# IFM_DuberFilter_ThroughHole_PCB_REV1a.net
KiCad netlist of a schematic drawn in EAGLE
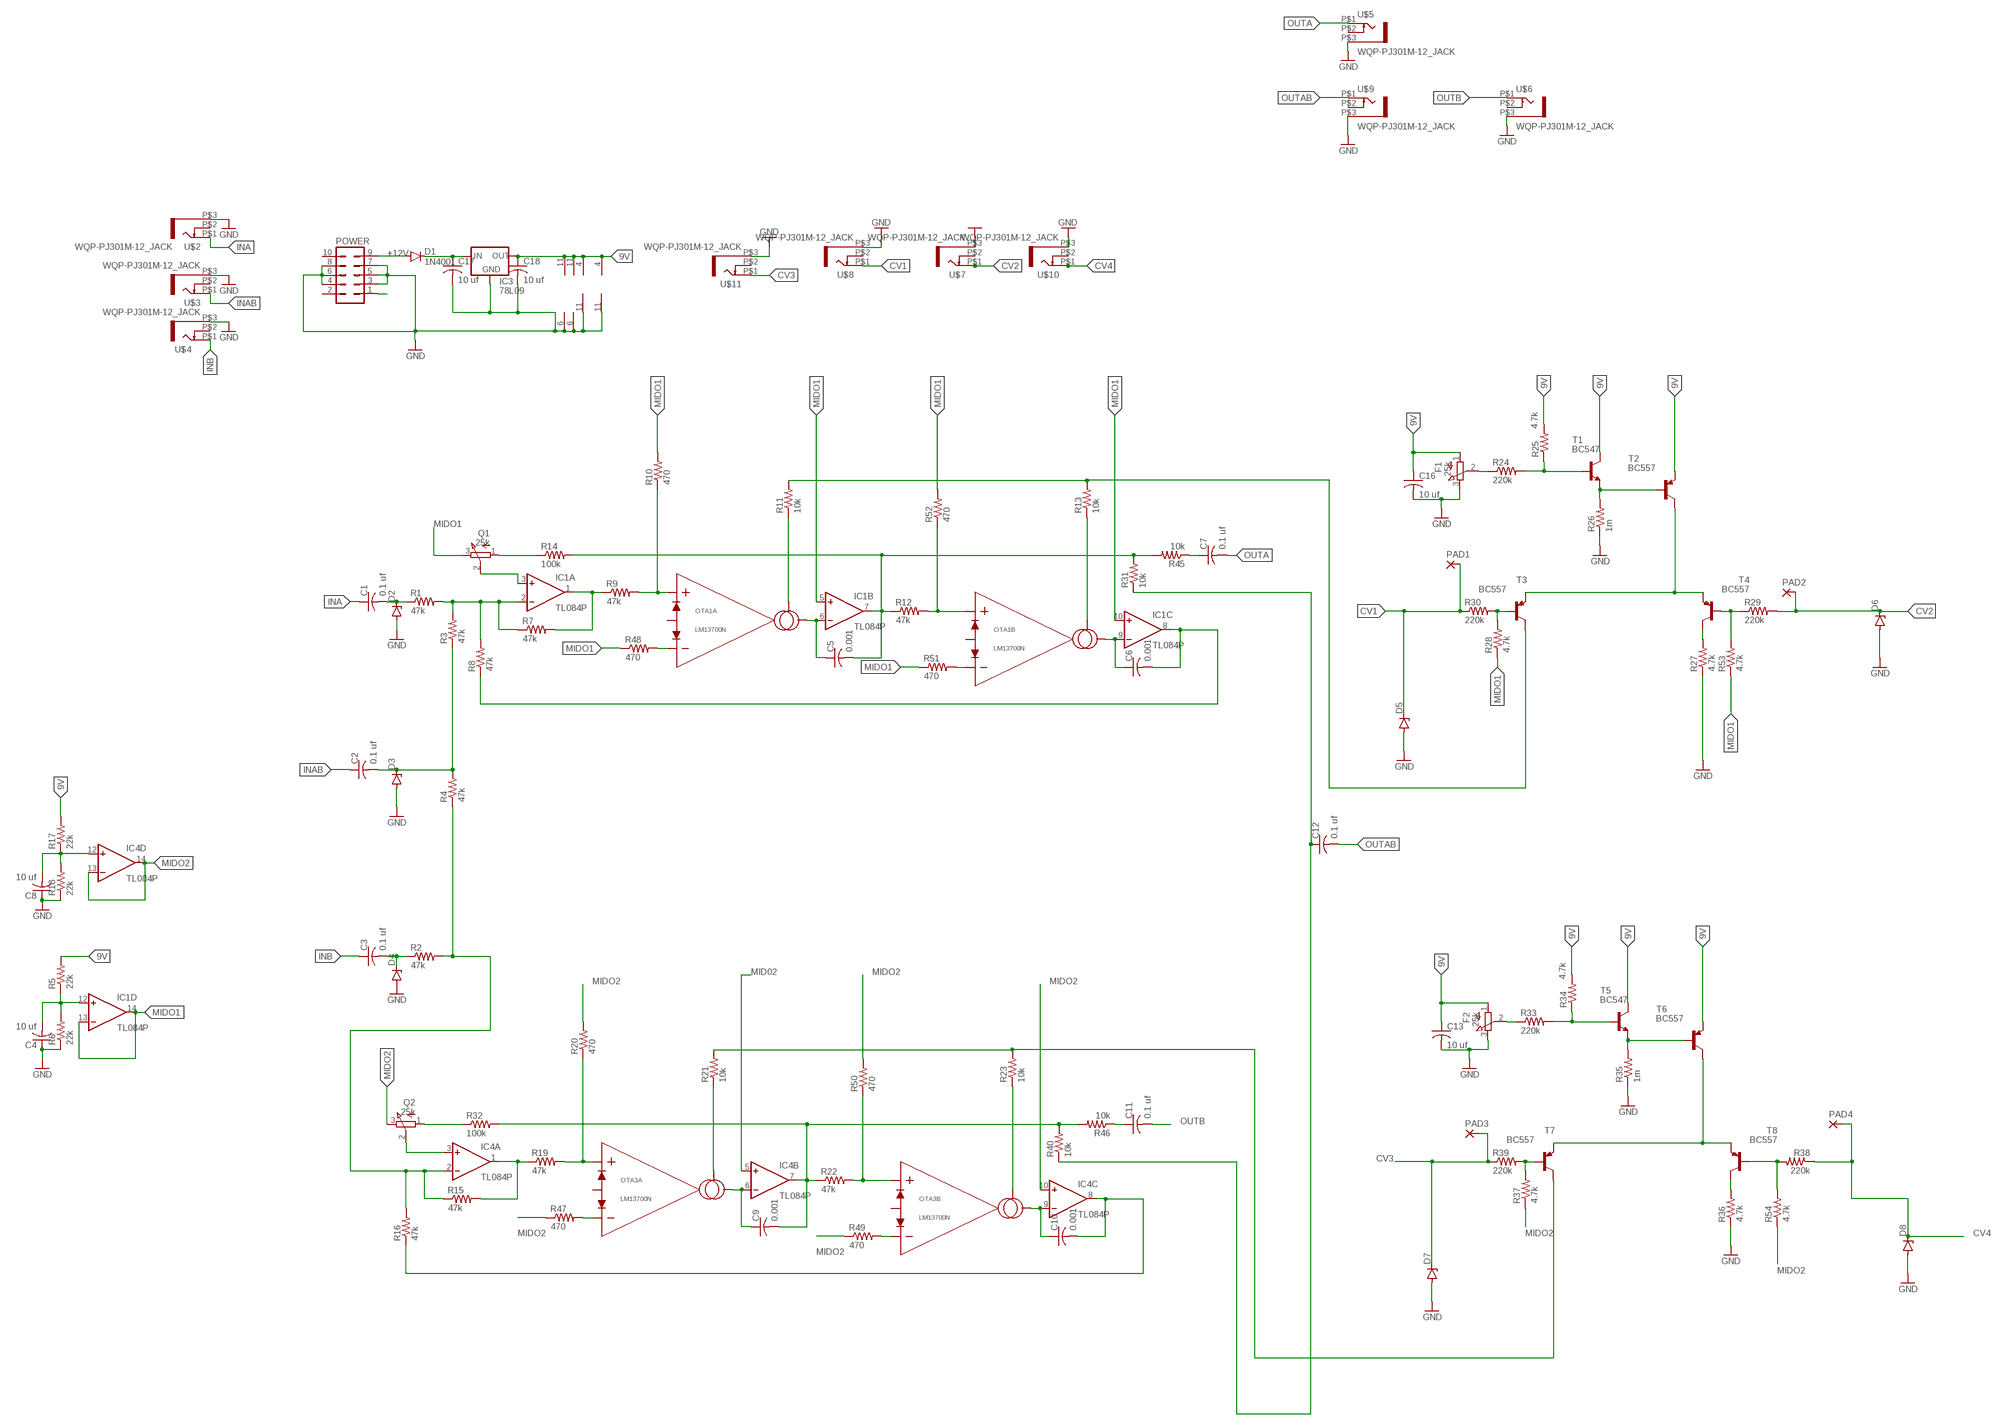
[diagram p0: schematic, sheet 1]

(export (version "E")
  (design (tool "Eeschema 10.0.6"))
  (components
    (comp (ref "C1")
      (value "0.1 uf")
      (footprint "eagle-import:C050-030X075")
      (libsource (lib "eagle-import") (part "C-US050-030X075"))
    )
    (comp (ref "C2")
      (value "0.1 uf")
      (footprint "eagle-import:C050-030X075")
      (libsource (lib "eagle-import") (part "C-US050-030X075"))
    )
    (comp (ref "C3")
      (value "0.1 uf")
      (footprint "eagle-import:C050-030X075")
      (libsource (lib "eagle-import") (part "C-US050-030X075"))
    )
    (comp (ref "C4")
      (value "10 uf")
      (footprint "eagle-import:C050-030X075")
      (libsource (lib "eagle-import") (part "C-US050-030X075"))
    )
    (comp (ref "C5")
      (value "0.001")
      (footprint "eagle-import:C050-030X075")
      (libsource (lib "eagle-import") (part "C-US050-030X075"))
    )
    (comp (ref "C6")
      (value "0.001")
      (footprint "eagle-import:C050-030X075")
      (libsource (lib "eagle-import") (part "C-US050-030X075"))
    )
    (comp (ref "C7")
      (value "0.1 uf")
      (footprint "eagle-import:C050-030X075")
      (libsource (lib "eagle-import") (part "C-US050-030X075"))
    )
    (comp (ref "C8")
      (value "10 uf")
      (footprint "eagle-import:C050-030X075")
      (libsource (lib "eagle-import") (part "C-US050-030X075"))
    )
    (comp (ref "C9")
      (value "0.001")
      (footprint "eagle-import:C050-030X075")
      (libsource (lib "eagle-import") (part "C-US050-030X075"))
    )
    (comp (ref "C10")
      (value "0.001")
      (footprint "eagle-import:C050-030X075")
      (libsource (lib "eagle-import") (part "C-US050-030X075"))
    )
    (comp (ref "C11")
      (value "0.1 uf")
      (footprint "eagle-import:C050-030X075")
      (libsource (lib "eagle-import") (part "C-US050-030X075"))
    )
    (comp (ref "C12")
      (value "0.1 uf")
      (footprint "eagle-import:C050-030X075")
      (libsource (lib "eagle-import") (part "C-US050-030X075"))
    )
    (comp (ref "C13")
      (value "10 uf")
      (footprint "eagle-import:C050-030X075")
      (libsource (lib "eagle-import") (part "C-US050-030X075"))
    )
    (comp (ref "C16")
      (value "10 uf")
      (footprint "eagle-import:C050-030X075")
      (libsource (lib "eagle-import") (part "C-US050-030X075"))
    )
    (comp (ref "C17")
      (value "10 uf")
      (footprint "eagle-import:C050-030X075")
      (libsource (lib "eagle-import") (part "C-US050-030X075"))
    )
    (comp (ref "C18")
      (value "10 uf")
      (footprint "eagle-import:C050-030X075")
      (libsource (lib "eagle-import") (part "C-US050-030X075"))
    )
    (comp (ref "D1")
      (value "1N4001")
      (footprint "eagle-import:DO41-10")
      (libsource (lib "eagle-import") (part "1N4004"))
    )
    (comp (ref "D2")
      (value "ZENER-DIODEDO34-7")
      (footprint "eagle-import:DO34Z7")
      (libsource (lib "eagle-import") (part "ZENER-DIODEDO34-7"))
    )
    (comp (ref "D3")
      (value "ZENER-DIODEDO34-7")
      (footprint "eagle-import:DO34Z7")
      (fields (field (name "SPICEPREFIX") "D"))
      (libsource (lib "eagle-import") (part "ZENER-DIODEDO34-7"))
    )
    (comp (ref "D4")
      (value "ZENER-DIODEDO34-7")
      (footprint "eagle-import:DO34Z7")
      (libsource (lib "eagle-import") (part "ZENER-DIODEDO34-7"))
    )
    (comp (ref "D5")
      (value "ZENER-DIODEDO34-7")
      (footprint "eagle-import:DO34Z7")
      (libsource (lib "eagle-import") (part "ZENER-DIODEDO34-7"))
    )
    (comp (ref "D6")
      (value "ZENER-DIODEDO34-7")
      (footprint "eagle-import:DO34Z7")
      (libsource (lib "eagle-import") (part "ZENER-DIODEDO34-7"))
    )
    (comp (ref "D7")
      (value "ZENER-DIODEDO34-7")
      (footprint "eagle-import:DO34Z7")
      (libsource (lib "eagle-import") (part "ZENER-DIODEDO34-7"))
    )
    (comp (ref "D8")
      (value "ZENER-DIODEDO34-7")
      (footprint "eagle-import:DO34Z7")
      (libsource (lib "eagle-import") (part "ZENER-DIODEDO34-7"))
    )
    (comp (ref "F1")
      (value "25k")
      (footprint "eagle-import:EVUFXL")
      (libsource (lib "eagle-import") (part "EVULF3"))
    )
    (comp (ref "F2")
      (value "25k")
      (footprint "eagle-import:EVUFXL")
      (libsource (lib "eagle-import") (part "EVULF3"))
    )
    (comp (ref "IC1")
      (value "TL084P")
      (footprint "eagle-import:DIL14")
      (libsource (lib "eagle-import") (part "TL084P"))
    )
    (comp (ref "IC3")
      (value "78L09")
      (footprint "eagle-import:78LXX")
      (libsource (lib "eagle-import") (part "78LXX"))
    )
    (comp (ref "IC4")
      (value "TL084P")
      (footprint "eagle-import:DIL14")
      (libsource (lib "eagle-import") (part "TL084P"))
    )
    (comp (ref "OTA1")
      (value "LM13700N")
      (footprint "eagle-import:DIP16")
      (libsource (lib "eagle-import") (part "LM13700N"))
    )
    (comp (ref "OTA3")
      (value "LM13700N")
      (footprint "eagle-import:DIP16")
      (libsource (lib "eagle-import") (part "LM13700N"))
    )
    (comp (ref "PAD1")
      (value "SMD2")
      (footprint "eagle-import:SMD1,27-2,54")
      (libsource (lib "eagle-import") (part "SMD2"))
    )
    (comp (ref "PAD2")
      (value "SMD2")
      (footprint "eagle-import:SMD1,27-2,54")
      (libsource (lib "eagle-import") (part "SMD2"))
    )
    (comp (ref "PAD3")
      (value "SMD2")
      (footprint "eagle-import:SMD1,27-2,54")
      (libsource (lib "eagle-import") (part "SMD2"))
    )
    (comp (ref "PAD4")
      (value "SMD2")
      (footprint "eagle-import:SMD1,27-2,54")
      (libsource (lib "eagle-import") (part "SMD2"))
    )
    (comp (ref "POWER")
      (value "10_PIN_HEADER")
      (footprint "eagle-import:MA05-2")
      (libsource (lib "eagle-import") (part "10_PIN_HEADER"))
    )
    (comp (ref "Q1")
      (value "25k")
      (footprint "eagle-import:EVUFXL")
      (libsource (lib "eagle-import") (part "EVULF3"))
    )
    (comp (ref "Q2")
      (value "25k")
      (footprint "eagle-import:EVUFXL")
      (libsource (lib "eagle-import") (part "EVULF3"))
    )
    (comp (ref "R1")
      (value "47k")
      (footprint "eagle-import:0204_7")
      (libsource (lib "eagle-import") (part "R-US_0204/7"))
    )
    (comp (ref "R2")
      (value "47k")
      (footprint "eagle-import:0204_7")
      (libsource (lib "eagle-import") (part "R-US_0204/7"))
    )
    (comp (ref "R3")
      (value "47k")
      (footprint "eagle-import:0204_7")
      (libsource (lib "eagle-import") (part "R-US_0204/7"))
    )
    (comp (ref "R4")
      (value "47k")
      (footprint "eagle-import:0204_7")
      (libsource (lib "eagle-import") (part "R-US_0204/7"))
    )
    (comp (ref "R5")
      (value "22k")
      (footprint "eagle-import:0204_7")
      (libsource (lib "eagle-import") (part "R-US_0204/7"))
    )
    (comp (ref "R6")
      (value "22k")
      (footprint "eagle-import:0204_7")
      (libsource (lib "eagle-import") (part "R-US_0204/7"))
    )
    (comp (ref "R7")
      (value "47k")
      (footprint "eagle-import:0204_7")
      (libsource (lib "eagle-import") (part "R-US_0204/7"))
    )
    (comp (ref "R8")
      (value "47k")
      (footprint "eagle-import:0204_7")
      (libsource (lib "eagle-import") (part "R-US_0204/7"))
    )
    (comp (ref "R9")
      (value "47k")
      (footprint "eagle-import:0204_7")
      (libsource (lib "eagle-import") (part "R-US_0204/7"))
    )
    (comp (ref "R10")
      (value "470")
      (footprint "eagle-import:0204_7")
      (libsource (lib "eagle-import") (part "R-US_0204/7"))
    )
    (comp (ref "R11")
      (value "10k")
      (footprint "eagle-import:0204_7")
      (libsource (lib "eagle-import") (part "R-US_0204/7"))
    )
    (comp (ref "R12")
      (value "47k")
      (footprint "eagle-import:0204_7")
      (libsource (lib "eagle-import") (part "R-US_0204/7"))
    )
    (comp (ref "R13")
      (value "10k")
      (footprint "eagle-import:0204_7")
      (libsource (lib "eagle-import") (part "R-US_0204/7"))
    )
    (comp (ref "R14")
      (value "100k")
      (footprint "eagle-import:0204_7")
      (libsource (lib "eagle-import") (part "R-US_0204/7"))
    )
    (comp (ref "R15")
      (value "47k")
      (footprint "eagle-import:0204_7")
      (libsource (lib "eagle-import") (part "R-US_0204/7"))
    )
    (comp (ref "R16")
      (value "47k")
      (footprint "eagle-import:0204_7")
      (libsource (lib "eagle-import") (part "R-US_0204/7"))
    )
    (comp (ref "R17")
      (value "22k")
      (footprint "eagle-import:0204_7")
      (libsource (lib "eagle-import") (part "R-US_0204/7"))
    )
    (comp (ref "R18")
      (value "22k")
      (footprint "eagle-import:0204_7")
      (libsource (lib "eagle-import") (part "R-US_0204/7"))
    )
    (comp (ref "R19")
      (value "47k")
      (footprint "eagle-import:0204_7")
      (libsource (lib "eagle-import") (part "R-US_0204/7"))
    )
    (comp (ref "R20")
      (value "470")
      (footprint "eagle-import:0204_7")
      (libsource (lib "eagle-import") (part "R-US_0204/7"))
    )
    (comp (ref "R21")
      (value "10k")
      (footprint "eagle-import:0204_7")
      (libsource (lib "eagle-import") (part "R-US_0204/7"))
    )
    (comp (ref "R22")
      (value "47k")
      (footprint "eagle-import:0204_7")
      (libsource (lib "eagle-import") (part "R-US_0204/7"))
    )
    (comp (ref "R23")
      (value "10k")
      (footprint "eagle-import:0204_7")
      (libsource (lib "eagle-import") (part "R-US_0204/7"))
    )
    (comp (ref "R24")
      (value "220k")
      (footprint "eagle-import:0204_7")
      (libsource (lib "eagle-import") (part "R-US_0204/7"))
    )
    (comp (ref "R25")
      (value "4.7k")
      (footprint "eagle-import:0204_7")
      (libsource (lib "eagle-import") (part "R-US_0204/7"))
    )
    (comp (ref "R26")
      (value "1m")
      (footprint "eagle-import:0204_7")
      (libsource (lib "eagle-import") (part "R-US_0204/7"))
    )
    (comp (ref "R27")
      (value "4.7k")
      (footprint "eagle-import:0204_7")
      (libsource (lib "eagle-import") (part "R-US_0204/7"))
    )
    (comp (ref "R28")
      (value "4.7k")
      (footprint "eagle-import:0204_7")
      (libsource (lib "eagle-import") (part "R-US_0204/7"))
    )
    (comp (ref "R29")
      (value "220k")
      (footprint "eagle-import:0204_7")
      (libsource (lib "eagle-import") (part "R-US_0204/7"))
    )
    (comp (ref "R30")
      (value "220k")
      (footprint "eagle-import:0204_7")
      (libsource (lib "eagle-import") (part "R-US_0204/7"))
    )
    (comp (ref "R31")
      (value "10k")
      (footprint "eagle-import:0204_7")
      (libsource (lib "eagle-import") (part "R-US_0204/7"))
    )
    (comp (ref "R32")
      (value "100k")
      (footprint "eagle-import:0204_7")
      (libsource (lib "eagle-import") (part "R-US_0204/7"))
    )
    (comp (ref "R33")
      (value "220k")
      (footprint "eagle-import:0204_7")
      (libsource (lib "eagle-import") (part "R-US_0204/7"))
    )
    (comp (ref "R34")
      (value "4.7k")
      (footprint "eagle-import:0204_7")
      (libsource (lib "eagle-import") (part "R-US_0204/7"))
    )
    (comp (ref "R35")
      (value "1m")
      (footprint "eagle-import:0204_7")
      (libsource (lib "eagle-import") (part "R-US_0204/7"))
    )
    (comp (ref "R36")
      (value "4.7k")
      (footprint "eagle-import:0204_7")
      (libsource (lib "eagle-import") (part "R-US_0204/7"))
    )
    (comp (ref "R37")
      (value "4.7k")
      (footprint "eagle-import:0204_7")
      (libsource (lib "eagle-import") (part "R-US_0204/7"))
    )
    (comp (ref "R38")
      (value "220k")
      (footprint "eagle-import:0204_7")
      (libsource (lib "eagle-import") (part "R-US_0204/7"))
    )
    (comp (ref "R39")
      (value "220k")
      (footprint "eagle-import:0204_7")
      (libsource (lib "eagle-import") (part "R-US_0204/7"))
    )
    (comp (ref "R40")
      (value "10k")
      (footprint "eagle-import:0204_7")
      (libsource (lib "eagle-import") (part "R-US_0204/7"))
    )
    (comp (ref "R45")
      (value "10k")
      (footprint "eagle-import:0204_7")
      (libsource (lib "eagle-import") (part "R-US_0204/7"))
    )
    (comp (ref "R46")
      (value "10k")
      (footprint "eagle-import:0204_7")
      (libsource (lib "eagle-import") (part "R-US_0204/7"))
    )
    (comp (ref "R47")
      (value "470")
      (footprint "eagle-import:0204_7")
      (libsource (lib "eagle-import") (part "R-US_0204/7"))
    )
    (comp (ref "R48")
      (value "470")
      (footprint "eagle-import:0204_7")
      (libsource (lib "eagle-import") (part "R-US_0204/7"))
    )
    (comp (ref "R49")
      (value "470")
      (footprint "eagle-import:0204_7")
      (libsource (lib "eagle-import") (part "R-US_0204/7"))
    )
    (comp (ref "R50")
      (value "470")
      (footprint "eagle-import:0204_7")
      (libsource (lib "eagle-import") (part "R-US_0204/7"))
    )
    (comp (ref "R51")
      (value "470")
      (footprint "eagle-import:0204_7")
      (libsource (lib "eagle-import") (part "R-US_0204/7"))
    )
    (comp (ref "R52")
      (value "470")
      (footprint "eagle-import:0204_7")
      (libsource (lib "eagle-import") (part "R-US_0204/7"))
    )
    (comp (ref "R53")
      (value "4.7k")
      (footprint "eagle-import:0204_7")
      (libsource (lib "eagle-import") (part "R-US_0204/7"))
    )
    (comp (ref "R54")
      (value "4.7k")
      (footprint "eagle-import:0204_7")
      (libsource (lib "eagle-import") (part "R-US_0204/7"))
    )
    (comp (ref "T1")
      (value "BC547")
      (footprint "eagle-import:TO92")
      (libsource (lib "eagle-import") (part "BC547"))
    )
    (comp (ref "T2")
      (value "BC557")
      (footprint "eagle-import:TO92-EBC")
      (libsource (lib "eagle-import") (part "-PNP-TO92-EBCBC557A"))
    )
    (comp (ref "T3")
      (value "BC557")
      (footprint "eagle-import:TO92-EBC")
      (libsource (lib "eagle-import") (part "-PNP-TO92-EBCBC557A"))
    )
    (comp (ref "T4")
      (value "BC557")
      (footprint "eagle-import:TO92-EBC")
      (libsource (lib "eagle-import") (part "-PNP-TO92-EBCBC557A"))
    )
    (comp (ref "T5")
      (value "BC547")
      (footprint "eagle-import:TO92")
      (libsource (lib "eagle-import") (part "BC547"))
    )
    (comp (ref "T6")
      (value "BC557")
      (footprint "eagle-import:TO92-EBC")
      (libsource (lib "eagle-import") (part "-PNP-TO92-EBCBC557A"))
    )
    (comp (ref "T7")
      (value "BC557")
      (footprint "eagle-import:TO92-EBC")
      (libsource (lib "eagle-import") (part "-PNP-TO92-EBCBC557A"))
    )
    (comp (ref "T8")
      (value "BC557")
      (footprint "eagle-import:TO92-EBC")
      (libsource (lib "eagle-import") (part "-PNP-TO92-EBCBC557A"))
    )
    (comp (ref "U$2")
      (value "WQP-PJ301M-12_JACK")
      (footprint "eagle-import:WQP-PJ301M-12_JACK")
      (libsource (lib "eagle-import") (part "WQP-PJ301M-12_JACK"))
    )
    (comp (ref "U$3")
      (value "WQP-PJ301M-12_JACK")
      (footprint "eagle-import:WQP-PJ301M-12_JACK")
      (libsource (lib "eagle-import") (part "WQP-PJ301M-12_JACK"))
    )
    (comp (ref "U$4")
      (value "WQP-PJ301M-12_JACK")
      (footprint "eagle-import:WQP-PJ301M-12_JACK")
      (libsource (lib "eagle-import") (part "WQP-PJ301M-12_JACK"))
    )
    (comp (ref "U$5")
      (value "WQP-PJ301M-12_JACK")
      (footprint "eagle-import:WQP-PJ301M-12_JACK")
      (libsource (lib "eagle-import") (part "WQP-PJ301M-12_JACK"))
    )
    (comp (ref "U$6")
      (value "WQP-PJ301M-12_JACK")
      (footprint "eagle-import:WQP-PJ301M-12_JACK")
      (libsource (lib "eagle-import") (part "WQP-PJ301M-12_JACK"))
    )
    (comp (ref "U$7")
      (value "WQP-PJ301M-12_JACK")
      (footprint "eagle-import:WQP-PJ301M-12_JACK")
      (libsource (lib "eagle-import") (part "WQP-PJ301M-12_JACK"))
    )
    (comp (ref "U$8")
      (value "WQP-PJ301M-12_JACK")
      (footprint "eagle-import:WQP-PJ301M-12_JACK")
      (libsource (lib "eagle-import") (part "WQP-PJ301M-12_JACK"))
    )
    (comp (ref "U$9")
      (value "WQP-PJ301M-12_JACK")
      (footprint "eagle-import:WQP-PJ301M-12_JACK")
      (libsource (lib "eagle-import") (part "WQP-PJ301M-12_JACK"))
    )
    (comp (ref "U$10")
      (value "WQP-PJ301M-12_JACK")
      (footprint "eagle-import:WQP-PJ301M-12_JACK")
      (libsource (lib "eagle-import") (part "WQP-PJ301M-12_JACK"))
    )
    (comp (ref "U$11")
      (value "WQP-PJ301M-12_JACK")
      (footprint "eagle-import:WQP-PJ301M-12_JACK")
      (libsource (lib "eagle-import") (part "WQP-PJ301M-12_JACK"))
    )
  )
  (nets
    (net (code "1") (name "/+12V") (class "Default")
      (node (ref "C17") (pin "1") (pinfunction "1_1") (pintype "passive"))
      (node (ref "D1") (pin "C") (pinfunction "C_C") (pintype "passive"))
      (node (ref "IC3") (pin "IN") (pinfunction "IN_IN") (pintype "input"))
    )
    (net (code "2") (name "/MID02") (class "Default")
      (node (ref "IC4") (pin "5") (pinfunction "+IN_5") (pintype "input"))
    )
    (net (code "3") (name "9V") (class "Default")
      (node (ref "C13") (pin "1") (pinfunction "1_1") (pintype "passive"))
      (node (ref "C16") (pin "1") (pinfunction "1_1") (pintype "passive"))
      (node (ref "C18") (pin "1") (pinfunction "1_1") (pintype "passive"))
      (node (ref "F1") (pin "1") (pinfunction "A_1") (pintype "passive"))
      (node (ref "F2") (pin "1") (pinfunction "A_1") (pintype "passive"))
      (node (ref "IC1") (pin "4") (pinfunction "V+_4") (pintype "power_in"))
      (node (ref "IC3") (pin "OUT") (pinfunction "OUT_OUT") (pintype "passive"))
      (node (ref "IC4") (pin "4") (pinfunction "V+_4") (pintype "power_in"))
      (node (ref "OTA1") (pin "11") (pinfunction "VCC_11") (pintype "power_in"))
      (node (ref "OTA3") (pin "11") (pinfunction "VCC_11") (pintype "power_in"))
      (node (ref "R17") (pin "2") (pinfunction "2_2") (pintype "passive"))
      (node (ref "R25") (pin "2") (pinfunction "2_2") (pintype "passive"))
      (node (ref "R34") (pin "2") (pinfunction "2_2") (pintype "passive"))
      (node (ref "R5") (pin "2") (pinfunction "2_2") (pintype "passive"))
      (node (ref "T1") (pin "3") (pinfunction "C_3") (pintype "passive"))
      (node (ref "T2") (pin "E") (pinfunction "E_E") (pintype "passive"))
      (node (ref "T5") (pin "3") (pinfunction "C_3") (pintype "passive"))
      (node (ref "T6") (pin "E") (pinfunction "E_E") (pintype "passive"))
    )
    (net (code "4") (name "CV1") (class "Default")
      (node (ref "D5") (pin "C") (pinfunction "C_C") (pintype "passive"))
      (node (ref "PAD1") (pin "1") (pinfunction "P_1") (pintype "passive"))
      (node (ref "R30") (pin "1") (pinfunction "1_1") (pintype "passive"))
      (node (ref "U$8") (pin "P$1") (pinfunction "2_P$1") (pintype "passive"))
    )
    (net (code "5") (name "CV2") (class "Default")
      (node (ref "D6") (pin "C") (pinfunction "C_C") (pintype "passive"))
      (node (ref "PAD2") (pin "1") (pinfunction "P_1") (pintype "passive"))
      (node (ref "R29") (pin "2") (pinfunction "2_2") (pintype "passive"))
      (node (ref "U$7") (pin "P$1") (pinfunction "2_P$1") (pintype "passive"))
    )
    (net (code "6") (name "CV3") (class "Default")
      (node (ref "D7") (pin "C") (pinfunction "C_C") (pintype "passive"))
      (node (ref "PAD3") (pin "1") (pinfunction "P_1") (pintype "passive"))
      (node (ref "R39") (pin "1") (pinfunction "1_1") (pintype "passive"))
      (node (ref "U$11") (pin "P$1") (pinfunction "2_P$1") (pintype "passive"))
    )
    (net (code "7") (name "CV4") (class "Default")
      (node (ref "D8") (pin "C") (pinfunction "C_C") (pintype "passive"))
      (node (ref "PAD4") (pin "1") (pinfunction "P_1") (pintype "passive"))
      (node (ref "R38") (pin "1") (pinfunction "1_1") (pintype "passive"))
      (node (ref "U$10") (pin "P$1") (pinfunction "2_P$1") (pintype "passive"))
    )
    (net (code "8") (name "GND") (class "Default")
      (node (ref "C13") (pin "2") (pinfunction "2_2") (pintype "passive"))
      (node (ref "C16") (pin "2") (pinfunction "2_2") (pintype "passive"))
      (node (ref "C17") (pin "2") (pinfunction "2_2") (pintype "passive"))
      (node (ref "C18") (pin "2") (pinfunction "2_2") (pintype "passive"))
      (node (ref "C4") (pin "1") (pinfunction "1_1") (pintype "passive"))
      (node (ref "C8") (pin "1") (pinfunction "1_1") (pintype "passive"))
      (node (ref "D2") (pin "A") (pinfunction "A_A") (pintype "passive"))
      (node (ref "D3") (pin "A") (pinfunction "A_A") (pintype "passive"))
      (node (ref "D4") (pin "A") (pinfunction "A_A") (pintype "passive"))
      (node (ref "D5") (pin "A") (pinfunction "A_A") (pintype "passive"))
      (node (ref "D6") (pin "A") (pinfunction "A_A") (pintype "passive"))
      (node (ref "D7") (pin "A") (pinfunction "A_A") (pintype "passive"))
      (node (ref "D8") (pin "A") (pinfunction "A_A") (pintype "passive"))
      (node (ref "F1") (pin "3") (pinfunction "E_3") (pintype "passive"))
      (node (ref "F2") (pin "3") (pinfunction "E_3") (pintype "passive"))
      (node (ref "IC1") (pin "11") (pinfunction "V-_11") (pintype "power_in"))
      (node (ref "IC3") (pin "GND") (pinfunction "GND_GND") (pintype "input"))
      (node (ref "IC4") (pin "11") (pinfunction "V-_11") (pintype "power_in"))
      (node (ref "OTA1") (pin "6") (pinfunction "VEE_6") (pintype "power_in"))
      (node (ref "OTA3") (pin "6") (pinfunction "VEE_6") (pintype "power_in"))
      (node (ref "POWER") (pin "3") (pinfunction "3_3") (pintype "passive"))
      (node (ref "POWER") (pin "4") (pinfunction "4_4") (pintype "passive"))
      (node (ref "POWER") (pin "5") (pinfunction "5_5") (pintype "passive"))
      (node (ref "POWER") (pin "6") (pinfunction "6_6") (pintype "passive"))
      (node (ref "POWER") (pin "7") (pinfunction "7_7") (pintype "passive"))
      (node (ref "POWER") (pin "8") (pinfunction "8_8") (pintype "passive"))
      (node (ref "R18") (pin "1") (pinfunction "1_1") (pintype "passive"))
      (node (ref "R26") (pin "1") (pinfunction "1_1") (pintype "passive"))
      (node (ref "R27") (pin "1") (pinfunction "1_1") (pintype "passive"))
      (node (ref "R35") (pin "1") (pinfunction "1_1") (pintype "passive"))
      (node (ref "R36") (pin "1") (pinfunction "1_1") (pintype "passive"))
      (node (ref "R6") (pin "1") (pinfunction "1_1") (pintype "passive"))
      (node (ref "U$10") (pin "P$3") (pinfunction "1_P$3") (pintype "passive"))
      (node (ref "U$11") (pin "P$3") (pinfunction "1_P$3") (pintype "passive"))
      (node (ref "U$2") (pin "P$3") (pinfunction "1_P$3") (pintype "passive"))
      (node (ref "U$3") (pin "P$3") (pinfunction "1_P$3") (pintype "passive"))
      (node (ref "U$4") (pin "P$3") (pinfunction "1_P$3") (pintype "passive"))
      (node (ref "U$5") (pin "P$3") (pinfunction "1_P$3") (pintype "passive"))
      (node (ref "U$6") (pin "P$3") (pinfunction "1_P$3") (pintype "passive"))
      (node (ref "U$7") (pin "P$3") (pinfunction "1_P$3") (pintype "passive"))
      (node (ref "U$8") (pin "P$3") (pinfunction "1_P$3") (pintype "passive"))
      (node (ref "U$9") (pin "P$3") (pinfunction "1_P$3") (pintype "passive"))
    )
    (net (code "9") (name "INA") (class "Default")
      (node (ref "C1") (pin "1") (pinfunction "1_1") (pintype "passive"))
      (node (ref "U$2") (pin "P$1") (pinfunction "2_P$1") (pintype "passive"))
    )
    (net (code "10") (name "INAB") (class "Default")
      (node (ref "C2") (pin "1") (pinfunction "1_1") (pintype "passive"))
      (node (ref "U$3") (pin "P$1") (pinfunction "2_P$1") (pintype "passive"))
    )
    (net (code "11") (name "INB") (class "Default")
      (node (ref "C3") (pin "1") (pinfunction "1_1") (pintype "passive"))
      (node (ref "U$4") (pin "P$1") (pinfunction "2_P$1") (pintype "passive"))
    )
    (net (code "12") (name "MIDO1") (class "Default")
      (node (ref "IC1") (pin "10") (pinfunction "+IN_10") (pintype "input"))
      (node (ref "IC1") (pin "13") (pinfunction "-IN_13") (pintype "input"))
      (node (ref "IC1") (pin "14") (pinfunction "OUT_14") (pintype "output"))
      (node (ref "IC1") (pin "5") (pinfunction "+IN_5") (pintype "input"))
      (node (ref "Q1") (pin "3") (pinfunction "E_3") (pintype "passive"))
      (node (ref "R10") (pin "2") (pinfunction "2_2") (pintype "passive"))
      (node (ref "R28") (pin "1") (pinfunction "1_1") (pintype "passive"))
      (node (ref "R48") (pin "1") (pinfunction "1_1") (pintype "passive"))
      (node (ref "R51") (pin "1") (pinfunction "1_1") (pintype "passive"))
      (node (ref "R52") (pin "2") (pinfunction "2_2") (pintype "passive"))
      (node (ref "R53") (pin "1") (pinfunction "1_1") (pintype "passive"))
    )
    (net (code "13") (name "MIDO2") (class "Default")
      (node (ref "IC4") (pin "10") (pinfunction "+IN_10") (pintype "input"))
      (node (ref "IC4") (pin "13") (pinfunction "-IN_13") (pintype "input"))
      (node (ref "IC4") (pin "14") (pinfunction "OUT_14") (pintype "output"))
      (node (ref "Q2") (pin "3") (pinfunction "E_3") (pintype "passive"))
      (node (ref "R20") (pin "2") (pinfunction "2_2") (pintype "passive"))
      (node (ref "R37") (pin "1") (pinfunction "1_1") (pintype "passive"))
      (node (ref "R47") (pin "1") (pinfunction "1_1") (pintype "passive"))
      (node (ref "R49") (pin "1") (pinfunction "1_1") (pintype "passive"))
      (node (ref "R50") (pin "2") (pinfunction "2_2") (pintype "passive"))
      (node (ref "R54") (pin "1") (pinfunction "1_1") (pintype "passive"))
    )
    (net (code "14") (name "Net-(C1-Pad2)") (class "Default")
      (node (ref "C1") (pin "2") (pinfunction "2_2") (pintype "passive"))
      (node (ref "D2") (pin "C") (pinfunction "C_C") (pintype "passive"))
      (node (ref "R1") (pin "1") (pinfunction "1_1") (pintype "passive"))
    )
    (net (code "15") (name "Net-(C2-Pad2)") (class "Default")
      (node (ref "C2") (pin "2") (pinfunction "2_2") (pintype "passive"))
      (node (ref "D3") (pin "C") (pinfunction "C_C") (pintype "passive"))
      (node (ref "R3") (pin "1") (pinfunction "1_1") (pintype "passive"))
      (node (ref "R4") (pin "2") (pinfunction "2_2") (pintype "passive"))
    )
    (net (code "16") (name "Net-(C3-Pad2)") (class "Default")
      (node (ref "C3") (pin "2") (pinfunction "2_2") (pintype "passive"))
      (node (ref "D4") (pin "C") (pinfunction "C_C") (pintype "passive"))
      (node (ref "R2") (pin "1") (pinfunction "1_1") (pintype "passive"))
    )
    (net (code "17") (name "Net-(C7-Pad1)") (class "Default")
      (node (ref "C7") (pin "1") (pinfunction "1_1") (pintype "passive"))
      (node (ref "R45") (pin "1") (pinfunction "1_1") (pintype "passive"))
    )
    (net (code "18") (name "Net-(C11-Pad1)") (class "Default")
      (node (ref "C11") (pin "1") (pinfunction "1_1") (pintype "passive"))
      (node (ref "R46") (pin "1") (pinfunction "1_1") (pintype "passive"))
    )
    (net (code "19") (name "Net-(C12-Pad1)") (class "Default")
      (node (ref "C12") (pin "1") (pinfunction "1_1") (pintype "passive"))
      (node (ref "R31") (pin "1") (pinfunction "1_1") (pintype "passive"))
      (node (ref "R40") (pin "1") (pinfunction "1_1") (pintype "passive"))
    )
    (net (code "20") (name "Net-(D1-PadA)") (class "Default")
      (node (ref "D1") (pin "A") (pinfunction "A_A") (pintype "passive"))
      (node (ref "POWER") (pin "9") (pinfunction "9_9") (pintype "passive"))
    )
    (net (code "21") (name "Net-(F1-S)") (class "Default")
      (node (ref "F1") (pin "2") (pinfunction "S_2") (pintype "passive"))
      (node (ref "R24") (pin "1") (pinfunction "1_1") (pintype "passive"))
    )
    (net (code "22") (name "Net-(F2-S)") (class "Default")
      (node (ref "F2") (pin "2") (pinfunction "S_2") (pintype "passive"))
      (node (ref "R33") (pin "1") (pinfunction "1_1") (pintype "passive"))
    )
    (net (code "23") (name "Net-(IC1A-+IN)") (class "Default")
      (node (ref "IC1") (pin "3") (pinfunction "+IN_3") (pintype "input"))
      (node (ref "Q1") (pin "2") (pinfunction "S_2") (pintype "passive"))
    )
    (net (code "24") (name "Net-(IC1A--IN)") (class "Default")
      (node (ref "IC1") (pin "2") (pinfunction "-IN_2") (pintype "input"))
      (node (ref "R1") (pin "2") (pinfunction "2_2") (pintype "passive"))
      (node (ref "R3") (pin "2") (pinfunction "2_2") (pintype "passive"))
      (node (ref "R7") (pin "1") (pinfunction "1_1") (pintype "passive"))
      (node (ref "R8") (pin "2") (pinfunction "2_2") (pintype "passive"))
    )
    (net (code "25") (name "Net-(IC1A-OUT)") (class "Default")
      (node (ref "IC1") (pin "1") (pinfunction "OUT_1") (pintype "output"))
      (node (ref "R7") (pin "2") (pinfunction "2_2") (pintype "passive"))
      (node (ref "R9") (pin "1") (pinfunction "1_1") (pintype "passive"))
    )
    (net (code "26") (name "Net-(IC1B--IN)") (class "Default")
      (node (ref "C5") (pin "1") (pinfunction "1_1") (pintype "passive"))
      (node (ref "IC1") (pin "6") (pinfunction "-IN_6") (pintype "input"))
      (node (ref "OTA1") (pin "5") (pinfunction "IOUT_5") (pintype "output"))
    )
    (net (code "27") (name "Net-(IC1B-OUT)") (class "Default")
      (node (ref "C5") (pin "2") (pinfunction "2_2") (pintype "passive"))
      (node (ref "IC1") (pin "7") (pinfunction "OUT_7") (pintype "output"))
      (node (ref "R12") (pin "1") (pinfunction "1_1") (pintype "passive"))
      (node (ref "R14") (pin "2") (pinfunction "2_2") (pintype "passive"))
      (node (ref "R31") (pin "2") (pinfunction "2_2") (pintype "passive"))
      (node (ref "R45") (pin "2") (pinfunction "2_2") (pintype "passive"))
    )
    (net (code "28") (name "Net-(IC1C--IN)") (class "Default")
      (node (ref "C6") (pin "1") (pinfunction "1_1") (pintype "passive"))
      (node (ref "IC1") (pin "9") (pinfunction "-IN_9") (pintype "input"))
      (node (ref "OTA1") (pin "12") (pinfunction "IOUT_12") (pintype "output"))
    )
    (net (code "29") (name "Net-(IC1C-OUT)") (class "Default")
      (node (ref "C6") (pin "2") (pinfunction "2_2") (pintype "passive"))
      (node (ref "IC1") (pin "8") (pinfunction "OUT_8") (pintype "output"))
      (node (ref "R8") (pin "1") (pinfunction "1_1") (pintype "passive"))
    )
    (net (code "30") (name "Net-(IC1D-+IN)") (class "Default")
      (node (ref "C4") (pin "2") (pinfunction "2_2") (pintype "passive"))
      (node (ref "IC1") (pin "12") (pinfunction "+IN_12") (pintype "input"))
      (node (ref "R5") (pin "1") (pinfunction "1_1") (pintype "passive"))
      (node (ref "R6") (pin "2") (pinfunction "2_2") (pintype "passive"))
    )
    (net (code "31") (name "Net-(IC4A-+IN)") (class "Default")
      (node (ref "IC4") (pin "3") (pinfunction "+IN_3") (pintype "input"))
      (node (ref "Q2") (pin "2") (pinfunction "S_2") (pintype "passive"))
    )
    (net (code "32") (name "Net-(IC4A--IN)") (class "Default")
      (node (ref "IC4") (pin "2") (pinfunction "-IN_2") (pintype "input"))
      (node (ref "R15") (pin "1") (pinfunction "1_1") (pintype "passive"))
      (node (ref "R16") (pin "2") (pinfunction "2_2") (pintype "passive"))
      (node (ref "R2") (pin "2") (pinfunction "2_2") (pintype "passive"))
      (node (ref "R4") (pin "1") (pinfunction "1_1") (pintype "passive"))
    )
    (net (code "33") (name "Net-(IC4A-OUT)") (class "Default")
      (node (ref "IC4") (pin "1") (pinfunction "OUT_1") (pintype "output"))
      (node (ref "R15") (pin "2") (pinfunction "2_2") (pintype "passive"))
      (node (ref "R19") (pin "1") (pinfunction "1_1") (pintype "passive"))
    )
    (net (code "34") (name "Net-(IC4B--IN)") (class "Default")
      (node (ref "C9") (pin "1") (pinfunction "1_1") (pintype "passive"))
      (node (ref "IC4") (pin "6") (pinfunction "-IN_6") (pintype "input"))
      (node (ref "OTA3") (pin "5") (pinfunction "IOUT_5") (pintype "output"))
    )
    (net (code "35") (name "Net-(IC4B-OUT)") (class "Default")
      (node (ref "C9") (pin "2") (pinfunction "2_2") (pintype "passive"))
      (node (ref "IC4") (pin "7") (pinfunction "OUT_7") (pintype "output"))
      (node (ref "R22") (pin "1") (pinfunction "1_1") (pintype "passive"))
      (node (ref "R32") (pin "2") (pinfunction "2_2") (pintype "passive"))
      (node (ref "R40") (pin "2") (pinfunction "2_2") (pintype "passive"))
      (node (ref "R46") (pin "2") (pinfunction "2_2") (pintype "passive"))
    )
    (net (code "36") (name "Net-(IC4C--IN)") (class "Default")
      (node (ref "C10") (pin "1") (pinfunction "1_1") (pintype "passive"))
      (node (ref "IC4") (pin "9") (pinfunction "-IN_9") (pintype "input"))
      (node (ref "OTA3") (pin "12") (pinfunction "IOUT_12") (pintype "output"))
    )
    (net (code "37") (name "Net-(IC4C-OUT)") (class "Default")
      (node (ref "C10") (pin "2") (pinfunction "2_2") (pintype "passive"))
      (node (ref "IC4") (pin "8") (pinfunction "OUT_8") (pintype "output"))
      (node (ref "R16") (pin "1") (pinfunction "1_1") (pintype "passive"))
    )
    (net (code "38") (name "Net-(IC4D-+IN)") (class "Default")
      (node (ref "C8") (pin "2") (pinfunction "2_2") (pintype "passive"))
      (node (ref "IC4") (pin "12") (pinfunction "+IN_12") (pintype "input"))
      (node (ref "R17") (pin "1") (pinfunction "1_1") (pintype "passive"))
      (node (ref "R18") (pin "2") (pinfunction "2_2") (pintype "passive"))
    )
    (net (code "39") (name "Net-(OTA1A-IABC)") (class "Default")
      (node (ref "OTA1") (pin "1") (pinfunction "IABC_1") (pintype "input"))
      (node (ref "R11") (pin "1") (pinfunction "1_1") (pintype "passive"))
    )
    (net (code "40") (name "Net-(OTA1A-IN+)") (class "Default")
      (node (ref "OTA1") (pin "3") (pinfunction "IN+_3") (pintype "input"))
      (node (ref "R10") (pin "1") (pinfunction "1_1") (pintype "passive"))
      (node (ref "R9") (pin "2") (pinfunction "2_2") (pintype "passive"))
    )
    (net (code "41") (name "Net-(OTA1A-IN-)") (class "Default")
      (node (ref "OTA1") (pin "4") (pinfunction "IN-_4") (pintype "input"))
      (node (ref "R48") (pin "2") (pinfunction "2_2") (pintype "passive"))
    )
    (net (code "42") (name "Net-(OTA1B-IABC)") (class "Default")
      (node (ref "OTA1") (pin "16") (pinfunction "IABC_16") (pintype "input"))
      (node (ref "R13") (pin "1") (pinfunction "1_1") (pintype "passive"))
    )
    (net (code "43") (name "Net-(OTA1B-IN+)") (class "Default")
      (node (ref "OTA1") (pin "14") (pinfunction "IN+_14") (pintype "input"))
      (node (ref "R12") (pin "2") (pinfunction "2_2") (pintype "passive"))
      (node (ref "R52") (pin "1") (pinfunction "1_1") (pintype "passive"))
    )
    (net (code "44") (name "Net-(OTA1B-IN-)") (class "Default")
      (node (ref "OTA1") (pin "13") (pinfunction "IN-_13") (pintype "input"))
      (node (ref "R51") (pin "2") (pinfunction "2_2") (pintype "passive"))
    )
    (net (code "45") (name "Net-(OTA3A-IABC)") (class "Default")
      (node (ref "OTA3") (pin "1") (pinfunction "IABC_1") (pintype "input"))
      (node (ref "R21") (pin "1") (pinfunction "1_1") (pintype "passive"))
    )
    (net (code "46") (name "Net-(OTA3A-IN+)") (class "Default")
      (node (ref "OTA3") (pin "3") (pinfunction "IN+_3") (pintype "input"))
      (node (ref "R19") (pin "2") (pinfunction "2_2") (pintype "passive"))
      (node (ref "R20") (pin "1") (pinfunction "1_1") (pintype "passive"))
    )
    (net (code "47") (name "Net-(OTA3A-IN-)") (class "Default")
      (node (ref "OTA3") (pin "4") (pinfunction "IN-_4") (pintype "input"))
      (node (ref "R47") (pin "2") (pinfunction "2_2") (pintype "passive"))
    )
    (net (code "48") (name "Net-(OTA3B-IABC)") (class "Default")
      (node (ref "OTA3") (pin "16") (pinfunction "IABC_16") (pintype "input"))
      (node (ref "R23") (pin "1") (pinfunction "1_1") (pintype "passive"))
    )
    (net (code "49") (name "Net-(OTA3B-IN+)") (class "Default")
      (node (ref "OTA3") (pin "14") (pinfunction "IN+_14") (pintype "input"))
      (node (ref "R22") (pin "2") (pinfunction "2_2") (pintype "passive"))
      (node (ref "R50") (pin "1") (pinfunction "1_1") (pintype "passive"))
    )
    (net (code "50") (name "Net-(OTA3B-IN-)") (class "Default")
      (node (ref "OTA3") (pin "13") (pinfunction "IN-_13") (pintype "input"))
      (node (ref "R49") (pin "2") (pinfunction "2_2") (pintype "passive"))
    )
    (net (code "51") (name "Net-(Q1-A)") (class "Default")
      (node (ref "Q1") (pin "1") (pinfunction "A_1") (pintype "passive"))
      (node (ref "R14") (pin "1") (pinfunction "1_1") (pintype "passive"))
    )
    (net (code "52") (name "Net-(Q2-A)") (class "Default")
      (node (ref "Q2") (pin "1") (pinfunction "A_1") (pintype "passive"))
      (node (ref "R32") (pin "1") (pinfunction "1_1") (pintype "passive"))
    )
    (net (code "53") (name "Net-(R11-Pad2)") (class "Default")
      (node (ref "R11") (pin "2") (pinfunction "2_2") (pintype "passive"))
      (node (ref "R13") (pin "2") (pinfunction "2_2") (pintype "passive"))
      (node (ref "T3") (pin "C") (pinfunction "C_C") (pintype "passive"))
    )
    (net (code "54") (name "Net-(R21-Pad2)") (class "Default")
      (node (ref "R21") (pin "2") (pinfunction "2_2") (pintype "passive"))
      (node (ref "R23") (pin "2") (pinfunction "2_2") (pintype "passive"))
      (node (ref "T7") (pin "C") (pinfunction "C_C") (pintype "passive"))
    )
    (net (code "55") (name "Net-(R27-Pad2)") (class "Default")
      (node (ref "R27") (pin "2") (pinfunction "2_2") (pintype "passive"))
      (node (ref "T4") (pin "C") (pinfunction "C_C") (pintype "passive"))
    )
    (net (code "56") (name "Net-(R28-Pad2)") (class "Default")
      (node (ref "R28") (pin "2") (pinfunction "2_2") (pintype "passive"))
      (node (ref "R30") (pin "2") (pinfunction "2_2") (pintype "passive"))
      (node (ref "T3") (pin "B") (pinfunction "B_B") (pintype "passive"))
    )
    (net (code "57") (name "Net-(R29-Pad1)") (class "Default")
      (node (ref "R29") (pin "1") (pinfunction "1_1") (pintype "passive"))
      (node (ref "R53") (pin "2") (pinfunction "2_2") (pintype "passive"))
      (node (ref "T4") (pin "B") (pinfunction "B_B") (pintype "passive"))
    )
    (net (code "58") (name "Net-(R36-Pad2)") (class "Default")
      (node (ref "R36") (pin "2") (pinfunction "2_2") (pintype "passive"))
      (node (ref "T8") (pin "C") (pinfunction "C_C") (pintype "passive"))
    )
    (net (code "59") (name "Net-(R37-Pad2)") (class "Default")
      (node (ref "R37") (pin "2") (pinfunction "2_2") (pintype "passive"))
      (node (ref "R39") (pin "2") (pinfunction "2_2") (pintype "passive"))
      (node (ref "T7") (pin "B") (pinfunction "B_B") (pintype "passive"))
    )
    (net (code "60") (name "Net-(R38-Pad2)") (class "Default")
      (node (ref "R38") (pin "2") (pinfunction "2_2") (pintype "passive"))
      (node (ref "R54") (pin "2") (pinfunction "2_2") (pintype "passive"))
      (node (ref "T8") (pin "B") (pinfunction "B_B") (pintype "passive"))
    )
    (net (code "61") (name "Net-(T1-B)") (class "Default")
      (node (ref "R24") (pin "2") (pinfunction "2_2") (pintype "passive"))
      (node (ref "R25") (pin "1") (pinfunction "1_1") (pintype "passive"))
      (node (ref "T1") (pin "2") (pinfunction "B_2") (pintype "passive"))
    )
    (net (code "62") (name "Net-(T1-E)") (class "Default")
      (node (ref "R26") (pin "2") (pinfunction "2_2") (pintype "passive"))
      (node (ref "T1") (pin "1") (pinfunction "E_1") (pintype "passive"))
      (node (ref "T2") (pin "B") (pinfunction "B_B") (pintype "passive"))
    )
    (net (code "63") (name "Net-(T2-PadC)") (class "Default")
      (node (ref "T2") (pin "C") (pinfunction "C_C") (pintype "passive"))
      (node (ref "T3") (pin "E") (pinfunction "E_E") (pintype "passive"))
      (node (ref "T4") (pin "E") (pinfunction "E_E") (pintype "passive"))
    )
    (net (code "64") (name "Net-(T5-B)") (class "Default")
      (node (ref "R33") (pin "2") (pinfunction "2_2") (pintype "passive"))
      (node (ref "R34") (pin "1") (pinfunction "1_1") (pintype "passive"))
      (node (ref "T5") (pin "2") (pinfunction "B_2") (pintype "passive"))
    )
    (net (code "65") (name "Net-(T5-E)") (class "Default")
      (node (ref "R35") (pin "2") (pinfunction "2_2") (pintype "passive"))
      (node (ref "T5") (pin "1") (pinfunction "E_1") (pintype "passive"))
      (node (ref "T6") (pin "B") (pinfunction "B_B") (pintype "passive"))
    )
    (net (code "66") (name "Net-(T6-PadC)") (class "Default")
      (node (ref "T6") (pin "C") (pinfunction "C_C") (pintype "passive"))
      (node (ref "T7") (pin "E") (pinfunction "E_E") (pintype "passive"))
      (node (ref "T8") (pin "E") (pinfunction "E_E") (pintype "passive"))
    )
    (net (code "67") (name "OUTA") (class "Default")
      (node (ref "C7") (pin "2") (pinfunction "2_2") (pintype "passive"))
      (node (ref "U$5") (pin "P$1") (pinfunction "2_P$1") (pintype "passive"))
    )
    (net (code "68") (name "OUTAB") (class "Default")
      (node (ref "C12") (pin "2") (pinfunction "2_2") (pintype "passive"))
      (node (ref "U$9") (pin "P$1") (pinfunction "2_P$1") (pintype "passive"))
    )
    (net (code "69") (name "OUTB") (class "Default")
      (node (ref "C11") (pin "2") (pinfunction "2_2") (pintype "passive"))
      (node (ref "U$6") (pin "P$1") (pinfunction "2_P$1") (pintype "passive"))
    )
    (net (code "70") (name "unconnected-(OTA1A-BIAS-Pad2)") (class "Default")
      (node (ref "OTA1") (pin "2") (pinfunction "BIAS_2") (pintype "input"))
    )
    (net (code "71") (name "unconnected-(OTA1B-BIAS-Pad15)") (class "Default")
      (node (ref "OTA1") (pin "15") (pinfunction "BIAS_15") (pintype "input"))
    )
    (net (code "72") (name "unconnected-(OTA3A-BIAS-Pad2)") (class "Default")
      (node (ref "OTA3") (pin "2") (pinfunction "BIAS_2") (pintype "input"))
    )
    (net (code "73") (name "unconnected-(OTA3B-BIAS-Pad15)") (class "Default")
      (node (ref "OTA3") (pin "15") (pinfunction "BIAS_15") (pintype "input"))
    )
    (net (code "74") (name "unconnected-(POWER-Pad1)") (class "Default")
      (node (ref "POWER") (pin "1") (pinfunction "1_1") (pintype "passive"))
    )
    (net (code "75") (name "unconnected-(POWER-Pad2)") (class "Default")
      (node (ref "POWER") (pin "2") (pinfunction "2_2") (pintype "passive"))
    )
    (net (code "76") (name "unconnected-(POWER-Pad10)") (class "Default")
      (node (ref "POWER") (pin "10") (pinfunction "10_10") (pintype "passive"))
    )
    (net (code "77") (name "unconnected-(U$2-3-PadP$2)") (class "Default")
      (node (ref "U$2") (pin "P$2") (pinfunction "3_P$2") (pintype "passive"))
    )
    (net (code "78") (name "unconnected-(U$3-3-PadP$2)") (class "Default")
      (node (ref "U$3") (pin "P$2") (pinfunction "3_P$2") (pintype "passive"))
    )
    (net (code "79") (name "unconnected-(U$4-3-PadP$2)") (class "Default")
      (node (ref "U$4") (pin "P$2") (pinfunction "3_P$2") (pintype "passive"))
    )
    (net (code "80") (name "unconnected-(U$5-3-PadP$2)") (class "Default")
      (node (ref "U$5") (pin "P$2") (pinfunction "3_P$2") (pintype "passive"))
    )
    (net (code "81") (name "unconnected-(U$6-3-PadP$2)") (class "Default")
      (node (ref "U$6") (pin "P$2") (pinfunction "3_P$2") (pintype "passive"))
    )
    (net (code "82") (name "unconnected-(U$7-3-PadP$2)") (class "Default")
      (node (ref "U$7") (pin "P$2") (pinfunction "3_P$2") (pintype "passive"))
    )
    (net (code "83") (name "unconnected-(U$8-3-PadP$2)") (class "Default")
      (node (ref "U$8") (pin "P$2") (pinfunction "3_P$2") (pintype "passive"))
    )
    (net (code "84") (name "unconnected-(U$9-3-PadP$2)") (class "Default")
      (node (ref "U$9") (pin "P$2") (pinfunction "3_P$2") (pintype "passive"))
    )
    (net (code "85") (name "unconnected-(U$10-3-PadP$2)") (class "Default")
      (node (ref "U$10") (pin "P$2") (pinfunction "3_P$2") (pintype "passive"))
    )
    (net (code "86") (name "unconnected-(U$11-3-PadP$2)") (class "Default")
      (node (ref "U$11") (pin "P$2") (pinfunction "3_P$2") (pintype "passive"))
    )
  )
)
